# BMS.net
KiCad netlist of a schematic drawn in Altium Designer
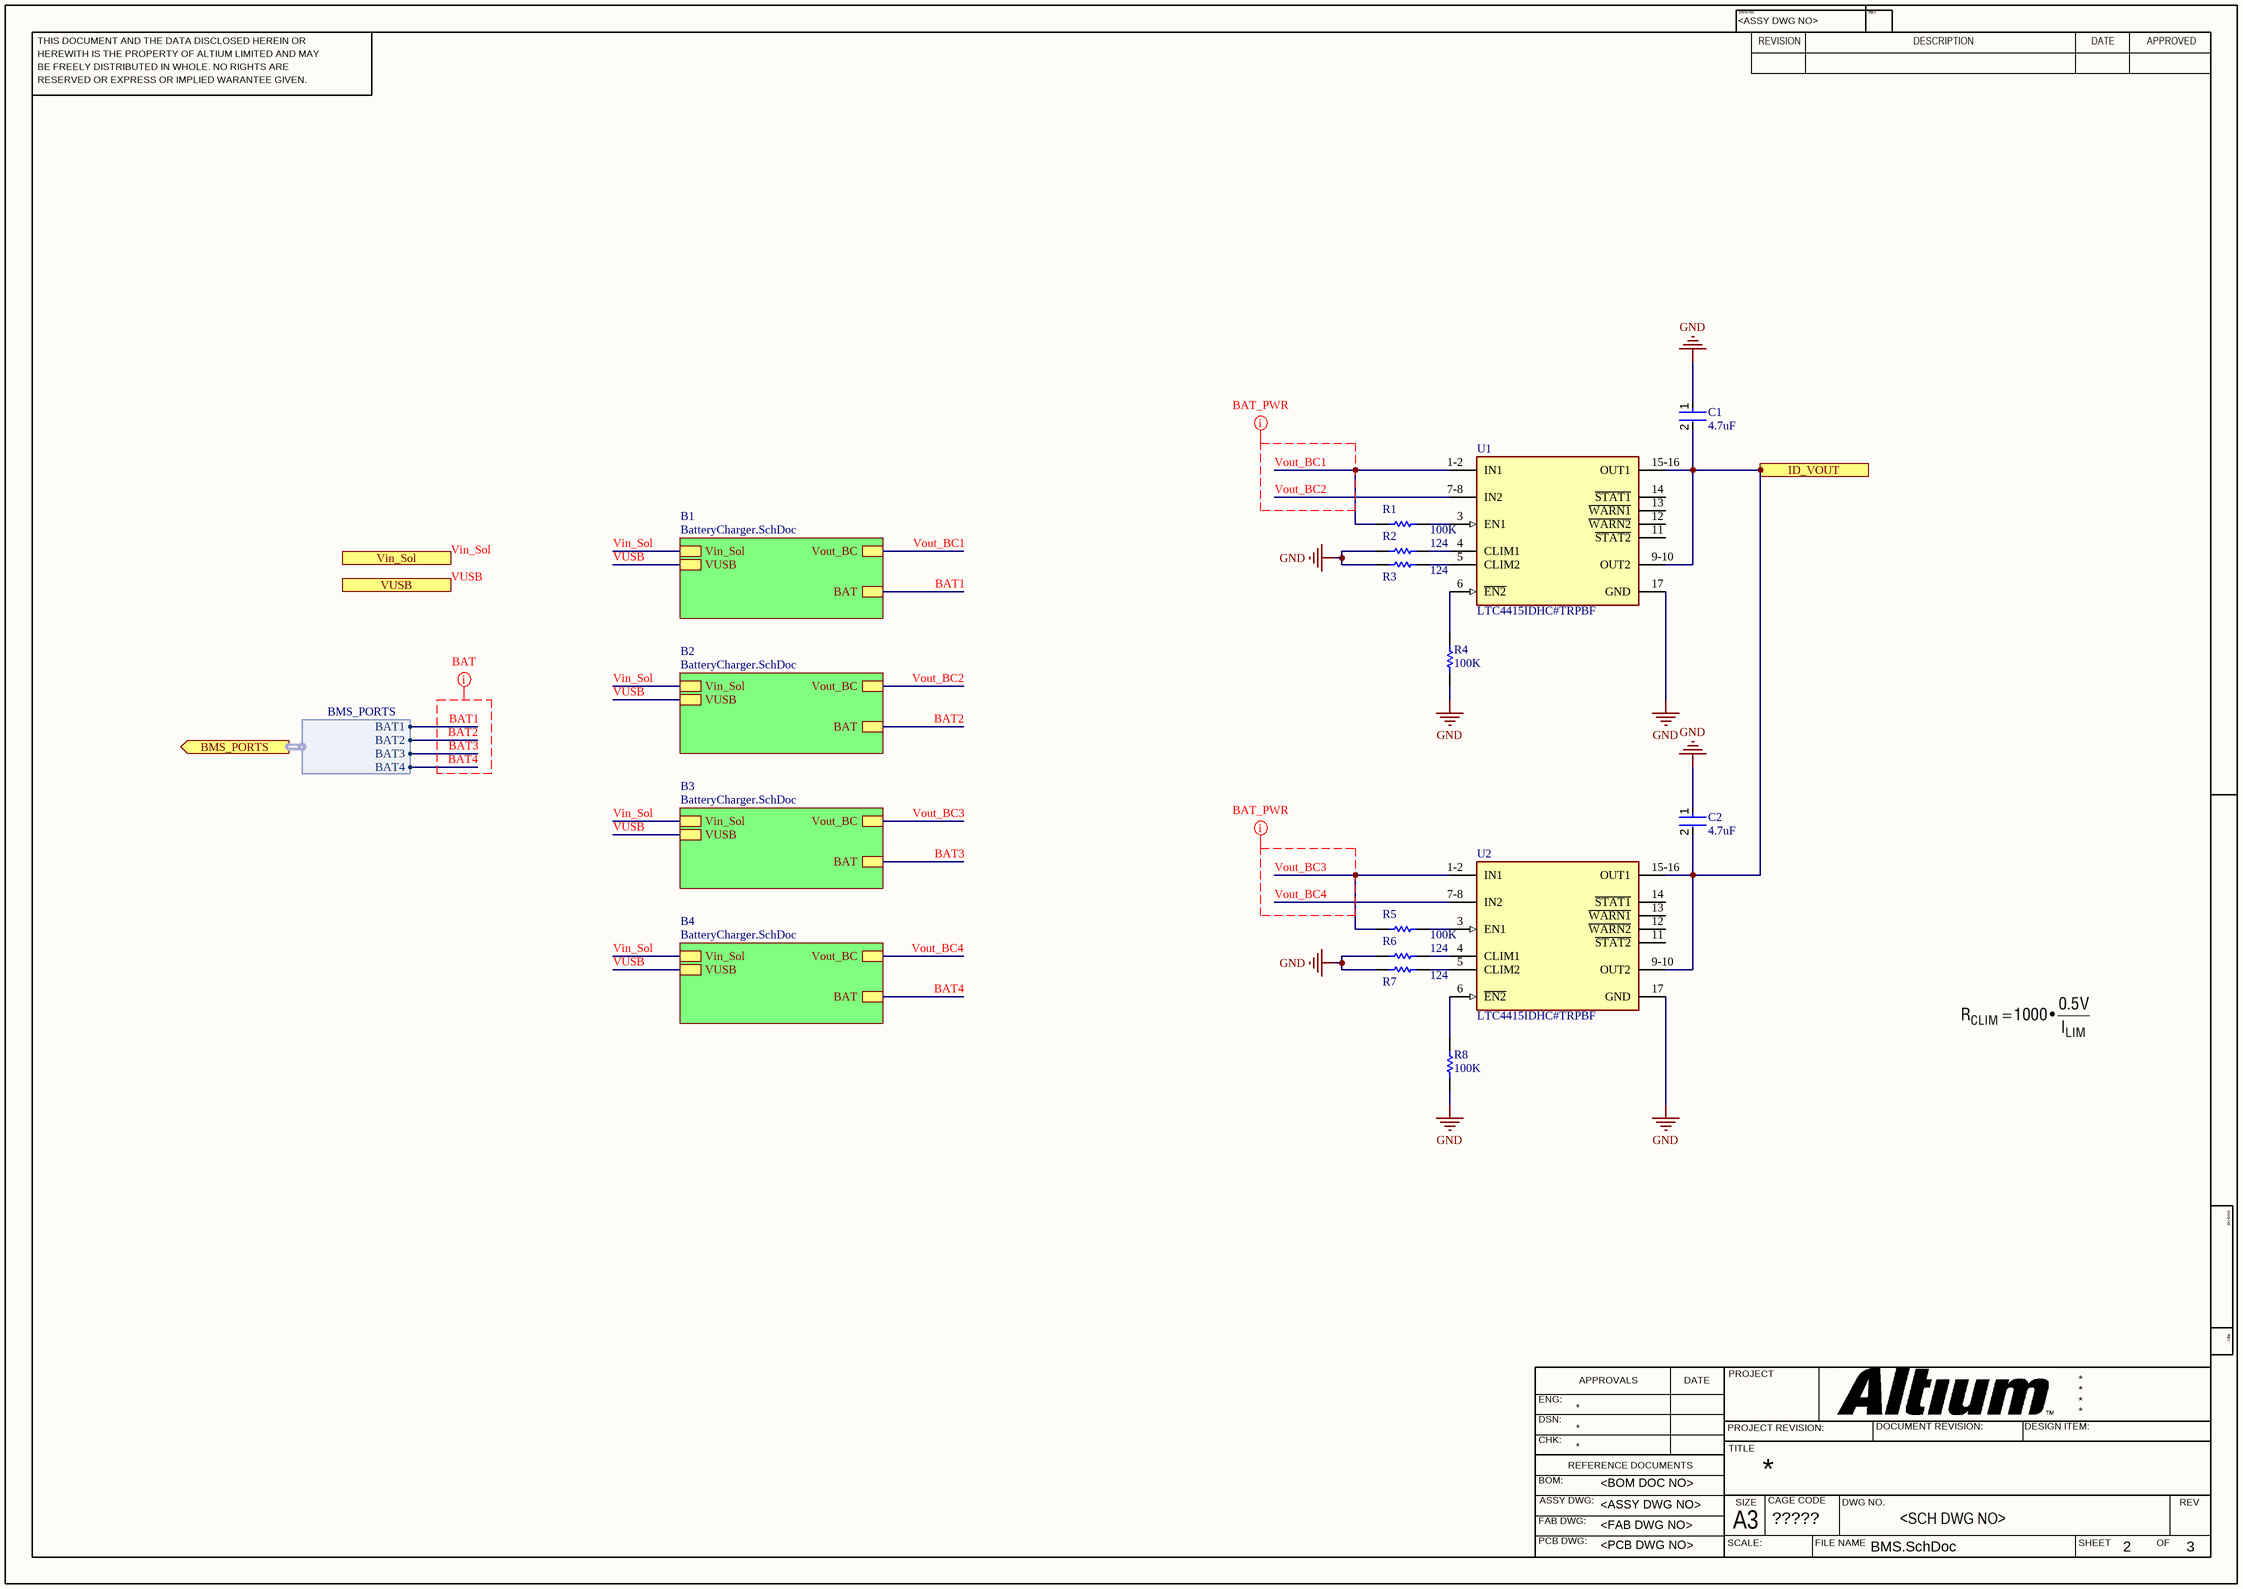
[diagram p0: BMS.SchDoc]

(export (version "E")
  (design (tool "Eeschema 10.0.6"))
  (components
    (comp (ref "C1")
      (value "4.7uF")
      (footprint "FP-GRM188-0_15-IPC_A")
      (description "CAP CER 4.7UF 10V X7S 0603")
      (fields (field (name "TOLERANCE") "10%"))
      (libsource (lib "Altium Content Vault") (part "02cd4be3c70576c341d710602a673aa"))
    )
    (comp (ref "C2")
      (value "4.7uF")
      (footprint "FP-GRM188-0_15-IPC_A")
      (description "CAP CER 4.7UF 10V X7S 0603")
      (fields (field (name "TOLERANCE") "10%"))
      (libsource (lib "Altium Content Vault") (part "02cd4be3c70576c341d710602a673aa"))
    )
    (comp (ref "R1")
      (value "100K")
      (footprint "RESC1608X55X30ML20T10")
      (fields (field (name "PART NUMBER") "RK73B1JTTD104J") (field (name "MANUFACTURER") "KOA Speer"))
      (libsource (lib "Altium Content Vault") (part "RES"))
    )
    (comp (ref "R2")
      (value "124")
      (footprint "RESC1608X55X30NL20T20")
      (fields (field (name "PART NUMBER") "ERA3AEB1240V") (field (name "MANUFACTURER") "Panasonic"))
      (libsource (lib "Altium Content Vault") (part "RES"))
    )
    (comp (ref "R3")
      (value "124")
      (footprint "RESC1608X55X30NL20T20")
      (fields (field (name "PART NUMBER") "ERA3AEB1240V") (field (name "MANUFACTURER") "Panasonic"))
      (libsource (lib "Altium Content Vault") (part "RES"))
    )
    (comp (ref "R4")
      (value "100K")
      (footprint "RESC1608X55X30ML20T10")
      (fields (field (name "PART NUMBER") "RK73B1JTTD104J") (field (name "MANUFACTURER") "KOA Speer"))
      (libsource (lib "Altium Content Vault") (part "RES"))
    )
    (comp (ref "R5")
      (value "100K")
      (footprint "RESC1608X55X30ML20T10")
      (fields (field (name "PART NUMBER") "RK73B1JTTD104J") (field (name "MANUFACTURER") "KOA Speer"))
      (libsource (lib "Altium Content Vault") (part "RES"))
    )
    (comp (ref "R6")
      (value "124")
      (footprint "RESC1608X55X30NL20T20")
      (fields (field (name "PART NUMBER") "ERA3AEB1240V") (field (name "MANUFACTURER") "Panasonic"))
      (libsource (lib "Altium Content Vault") (part "RES"))
    )
    (comp (ref "R7")
      (value "124")
      (footprint "RESC1608X55X30NL20T20")
      (fields (field (name "PART NUMBER") "ERA3AEB1240V") (field (name "MANUFACTURER") "Panasonic"))
      (libsource (lib "Altium Content Vault") (part "RES"))
    )
    (comp (ref "R8")
      (value "100K")
      (footprint "RESC1608X55X30ML20T10")
      (fields (field (name "PART NUMBER") "RK73B1JTTD104J") (field (name "MANUFACTURER") "KOA Speer"))
      (libsource (lib "Altium Content Vault") (part "RES"))
    )
    (comp (ref "U1")
      (value "LTC4415IDHC#TRPBF")
      (footprint "FP-DHC-16-05-08-1872-MFG")
      (description "IC OR CTRLR SRC SELECT 16DFN")
      (libsource (lib "Altium Content Vault") (part "5e765bd52b7ac5a67e044379f5406d3"))
    )
    (comp (ref "U2")
      (value "LTC4415IDHC#TRPBF")
      (footprint "FP-DHC-16-05-08-1872-MFG")
      (description "IC OR CTRLR SRC SELECT 16DFN")
      (libsource (lib "Altium Content Vault") (part "5e765bd52b7ac5a67e044379f5406d3"))
    )
  )
  (nets
    (net (code "6") (name "/ID_VOUT") (class "Default")
      (node (ref "C1") (pin "2") (pinfunction "2_2") (pintype "passive"))
      (node (ref "C2") (pin "2") (pinfunction "2_2") (pintype "passive"))
      (node (ref "U1") (pin "15-16") (pinfunction "OUT1_15-16") (pintype "passive"))
      (node (ref "U1") (pin "9-10") (pinfunction "OUT2_9-10") (pintype "passive"))
      (node (ref "U2") (pin "15-16") (pinfunction "OUT1_15-16") (pintype "passive"))
      (node (ref "U2") (pin "9-10") (pinfunction "OUT2_9-10") (pintype "passive"))
    )
    (net (code "9") (name "/Vout_BC1") (class "Default")
      (node (ref "R1") (pin "2") (pinfunction "2_2") (pintype "passive"))
      (node (ref "U1") (pin "1-2") (pinfunction "IN1_1-2") (pintype "power_in"))
    )
    (net (code "10") (name "/Vout_BC2") (class "Default")
      (node (ref "U1") (pin "7-8") (pinfunction "IN2_7-8") (pintype "power_in"))
    )
    (net (code "11") (name "/Vout_BC3") (class "Default")
      (node (ref "R5") (pin "2") (pinfunction "2_2") (pintype "passive"))
      (node (ref "U2") (pin "1-2") (pinfunction "IN1_1-2") (pintype "power_in"))
    )
    (net (code "12") (name "/Vout_BC4") (class "Default")
      (node (ref "U2") (pin "7-8") (pinfunction "IN2_7-8") (pintype "power_in"))
    )
    (net (code "14") (name "GND") (class "Default")
      (node (ref "C1") (pin "1") (pinfunction "1_1") (pintype "passive"))
      (node (ref "C2") (pin "1") (pinfunction "1_1") (pintype "passive"))
      (node (ref "R2") (pin "1") (pinfunction "1_1") (pintype "passive"))
      (node (ref "R3") (pin "1") (pinfunction "1_1") (pintype "passive"))
      (node (ref "R4") (pin "2") (pinfunction "2_2") (pintype "passive"))
      (node (ref "R6") (pin "1") (pinfunction "1_1") (pintype "passive"))
      (node (ref "R7") (pin "1") (pinfunction "1_1") (pintype "passive"))
      (node (ref "R8") (pin "2") (pinfunction "2_2") (pintype "passive"))
      (node (ref "U1") (pin "17") (pinfunction "GND_17") (pintype "power_in"))
      (node (ref "U2") (pin "17") (pinfunction "GND_17") (pintype "power_in"))
    )
    (net (code "15") (name "Net-(U1-CLIM1)") (class "Default")
      (node (ref "R2") (pin "2") (pinfunction "2_2") (pintype "passive"))
      (node (ref "U1") (pin "4") (pinfunction "CLIM1_4") (pintype "passive"))
    )
    (net (code "16") (name "Net-(U1-CLIM2)") (class "Default")
      (node (ref "R3") (pin "2") (pinfunction "2_2") (pintype "passive"))
      (node (ref "U1") (pin "5") (pinfunction "CLIM2_5") (pintype "passive"))
    )
    (net (code "17") (name "Net-(U1-EN1)") (class "Default")
      (node (ref "R1") (pin "1") (pinfunction "1_1") (pintype "passive"))
      (node (ref "U1") (pin "3") (pinfunction "EN1_3") (pintype "input"))
    )
    (net (code "18") (name "Net-(U1-~{EN2})") (class "Default")
      (node (ref "R4") (pin "1") (pinfunction "1_1") (pintype "passive"))
      (node (ref "U1") (pin "6") (pinfunction "~{EN2}_6") (pintype "input"))
    )
    (net (code "19") (name "Net-(U2-CLIM1)") (class "Default")
      (node (ref "R6") (pin "2") (pinfunction "2_2") (pintype "passive"))
      (node (ref "U2") (pin "4") (pinfunction "CLIM1_4") (pintype "passive"))
    )
    (net (code "20") (name "Net-(U2-CLIM2)") (class "Default")
      (node (ref "R7") (pin "2") (pinfunction "2_2") (pintype "passive"))
      (node (ref "U2") (pin "5") (pinfunction "CLIM2_5") (pintype "passive"))
    )
    (net (code "21") (name "Net-(U2-EN1)") (class "Default")
      (node (ref "R5") (pin "1") (pinfunction "1_1") (pintype "passive"))
      (node (ref "U2") (pin "3") (pinfunction "EN1_3") (pintype "input"))
    )
    (net (code "22") (name "Net-(U2-~{EN2})") (class "Default")
      (node (ref "R8") (pin "1") (pinfunction "1_1") (pintype "passive"))
      (node (ref "U2") (pin "6") (pinfunction "~{EN2}_6") (pintype "input"))
    )
    (net (code "23") (name "unconnected-(U1-~{STAT1}-Pad14)") (class "Default")
      (node (ref "U1") (pin "14") (pinfunction "~{STAT1}_14") (pintype "open_collector"))
    )
    (net (code "24") (name "unconnected-(U1-~{STAT2}-Pad11)") (class "Default")
      (node (ref "U1") (pin "11") (pinfunction "~{STAT2}_11") (pintype "open_collector"))
    )
    (net (code "25") (name "unconnected-(U1-~{WARN1}-Pad13)") (class "Default")
      (node (ref "U1") (pin "13") (pinfunction "~{WARN1}_13") (pintype "open_collector"))
    )
    (net (code "26") (name "unconnected-(U1-~{WARN2}-Pad12)") (class "Default")
      (node (ref "U1") (pin "12") (pinfunction "~{WARN2}_12") (pintype "open_collector"))
    )
    (net (code "27") (name "unconnected-(U2-~{STAT1}-Pad14)") (class "Default")
      (node (ref "U2") (pin "14") (pinfunction "~{STAT1}_14") (pintype "open_collector"))
    )
    (net (code "28") (name "unconnected-(U2-~{STAT2}-Pad11)") (class "Default")
      (node (ref "U2") (pin "11") (pinfunction "~{STAT2}_11") (pintype "open_collector"))
    )
    (net (code "29") (name "unconnected-(U2-~{WARN1}-Pad13)") (class "Default")
      (node (ref "U2") (pin "13") (pinfunction "~{WARN1}_13") (pintype "open_collector"))
    )
    (net (code "30") (name "unconnected-(U2-~{WARN2}-Pad12)") (class "Default")
      (node (ref "U2") (pin "12") (pinfunction "~{WARN2}_12") (pintype "open_collector"))
    )
  )
)
